# MotorCircuit.net
KiCad netlist of a schematic drawn in Altium Designer
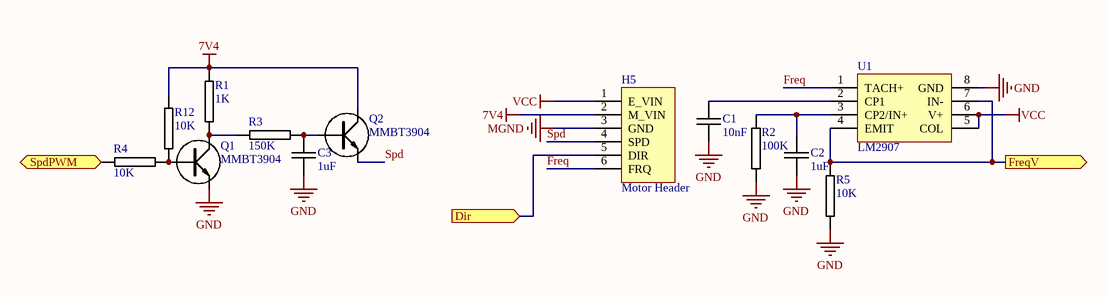
[diagram p0: MotorCircuit.SchDoc]

(export (version "E")
  (design (tool "Eeschema 10.0.6"))
  (components
    (comp (ref "C1")
      (value "10nF")
      (footprint "0805C-TBD")
      (description "CAPACITOR 0805 CERAMIC")
      (libsource (lib "vh_altium_library") (part "0805C-100nF-25V-X7R-MUR"))
    )
    (comp (ref "C2")
      (value "1uF")
      (footprint "0805C-GENERIC")
      (description "CAPACITOR 0805 CERAMIC")
      (fields (field (name "TOLERANCE") "±20%") (field (name "MANUFACTURER") "Panasonic - ECG"))
      (libsource (lib "vh_altium_library") (part "0805C-10UF-6V3-X5R-PAN"))
    )
    (comp (ref "C3")
      (value "1uF")
      (footprint "0805C-GENERIC")
      (description "CAPACITOR 0805 CERAMIC")
      (fields
        (field (name "MANUFACTURER PART NUMBER") "ECJ-1VB0J225K")
        (field (name "MANUFACTURER") "Panasonic - ECG")
      )
      (libsource (lib "vh_altium_library") (part "0805C-2U2-6V3-X5R-PAN"))
    )
    (comp (ref "H5")
      (value "Motor Header")
      (footprint "Motor Header")
      (libsource (lib "RWSComponents") (part "Motor Header"))
    )
    (comp (ref "Q1")
      (value "MMBT3904")
      (footprint "SOT23-BCE")
      (description "BC847 SMALL SIGNAL NPN TRANSISTOR")
      (libsource (lib "vh_altium_library") (part "MMBT2222"))
    )
    (comp (ref "Q2")
      (value "MMBT3904")
      (footprint "SOT23-BCE")
      (description "BC847 SMALL SIGNAL NPN TRANSISTOR")
      (libsource (lib "vh_altium_library") (part "MMBT2222"))
    )
    (comp (ref "R1")
      (value "1K")
      (footprint "0805R-1K")
      (description "RESISTOR 0805 1/4 WATT THIN FILM")
      (libsource (lib "vh_altium_library") (part "0805R-1K"))
    )
    (comp (ref "R2")
      (value "100K")
      (footprint "0805R-100K")
      (description "RESISTOR 0805 1/4 WATT THIN FILM")
      (libsource (lib "vh_altium_library") (part "0805R-100K"))
    )
    (comp (ref "R3")
      (value "150K")
      (footprint "0805R-150K")
      (description "RESISTOR 0805 1/4 WATT THIN FILM")
      (libsource (lib "vh_altium_library") (part "0805R-150K"))
    )
    (comp (ref "R4")
      (value "10K")
      (footprint "0805R-10K")
      (description "RESISTOR 0805 1/4 WATT THIN FILM")
      (libsource (lib "vh_altium_library") (part "0805R-10K"))
    )
    (comp (ref "R5")
      (value "10K")
      (footprint "0805R-10K")
      (description "RESISTOR 0805 1/4 WATT THIN FILM")
      (libsource (lib "vh_altium_library") (part "0805R-10K"))
    )
    (comp (ref "R12")
      (value "10K")
      (footprint "0805R-10K")
      (description "RESISTOR 0805 1/4 WATT THIN FILM")
      (libsource (lib "vh_altium_library") (part "0805R-10K"))
    )
    (comp (ref "U1")
      (value "LM2907")
      (footprint "LM2907")
      (description "Freq to Voltage Converter")
      (libsource (lib "RWSComponents") (part "LM2907"))
    )
  )
  (nets
    (net (code "1") (name "/Dir") (class "Default")
      (node (ref "H5") (pin "5") (pinfunction "DIR_5") (pintype "passive"))
    )
    (net (code "2") (name "/Freq") (class "Default")
      (node (ref "H5") (pin "6") (pinfunction "FRQ_6") (pintype "passive"))
      (node (ref "U1") (pin "1") (pinfunction "TACH+_1") (pintype "passive"))
    )
    (net (code "3") (name "/FreqV") (class "Default")
      (node (ref "R5") (pin "1") (pintype "passive"))
      (node (ref "U1") (pin "4") (pinfunction "EMIT_4") (pintype "passive"))
      (node (ref "U1") (pin "7") (pinfunction "IN-_7") (pintype "passive"))
    )
    (net (code "4") (name "/Spd") (class "Default")
      (node (ref "H5") (pin "4") (pinfunction "SPD_4") (pintype "passive"))
      (node (ref "Q2") (pin "E") (pintype "passive"))
    )
    (net (code "5") (name "/SpdPWM") (class "Default") (node (ref "R4") (pin "1") (pintype "passive")))
    (net (code "6") (name "7V4") (class "Default")
      (node (ref "H5") (pin "2") (pinfunction "M_VIN_2") (pintype "passive"))
      (node (ref "Q2") (pin "C") (pintype "passive"))
      (node (ref "R1") (pin "1") (pintype "passive"))
      (node (ref "R12") (pin "2") (pintype "passive"))
    )
    (net (code "7") (name "GND") (class "Default")
      (node (ref "C1") (pin "2") (pintype "passive"))
      (node (ref "C2") (pin "2") (pintype "passive"))
      (node (ref "C3") (pin "2") (pintype "passive"))
      (node (ref "Q1") (pin "E") (pintype "passive"))
      (node (ref "R2") (pin "2") (pintype "passive"))
      (node (ref "R5") (pin "2") (pintype "passive"))
      (node (ref "U1") (pin "8") (pinfunction "GND_8") (pintype "passive"))
    )
    (net (code "8") (name "MGND") (class "Default")
      (node (ref "H5") (pin "3") (pinfunction "GND_3") (pintype "passive"))
    )
    (net (code "9") (name "Net-(C3-Pad1)") (class "Default")
      (node (ref "C3") (pin "1") (pintype "passive"))
      (node (ref "Q2") (pin "B") (pintype "passive"))
      (node (ref "R3") (pin "2") (pintype "passive"))
    )
    (net (code "10") (name "Net-(Q1-PadB)") (class "Default")
      (node (ref "Q1") (pin "B") (pintype "passive"))
      (node (ref "R12") (pin "1") (pintype "passive"))
      (node (ref "R4") (pin "2") (pintype "passive"))
    )
    (net (code "11") (name "Net-(Q1-PadC)") (class "Default")
      (node (ref "Q1") (pin "C") (pintype "passive"))
      (node (ref "R1") (pin "2") (pintype "passive"))
      (node (ref "R3") (pin "1") (pintype "passive"))
    )
    (net (code "12") (name "Net-(U1-CP1)") (class "Default")
      (node (ref "C1") (pin "1") (pintype "passive"))
      (node (ref "U1") (pin "2") (pinfunction "CP1_2") (pintype "passive"))
    )
    (net (code "13") (name "Net-(U1-CP2{slash}IN+)") (class "Default")
      (node (ref "C2") (pin "1") (pintype "passive"))
      (node (ref "R2") (pin "1") (pintype "passive"))
      (node (ref "U1") (pin "3") (pinfunction "CP2/IN+_3") (pintype "passive"))
    )
    (net (code "14") (name "VCC") (class "Default")
      (node (ref "H5") (pin "1") (pinfunction "E_VIN_1") (pintype "passive"))
      (node (ref "U1") (pin "5") (pinfunction "COL_5") (pintype "passive"))
      (node (ref "U1") (pin "6") (pinfunction "V+_6") (pintype "passive"))
    )
  )
)
